# Dev_Board.net
KiCad netlist of a schematic drawn in Altium Designer
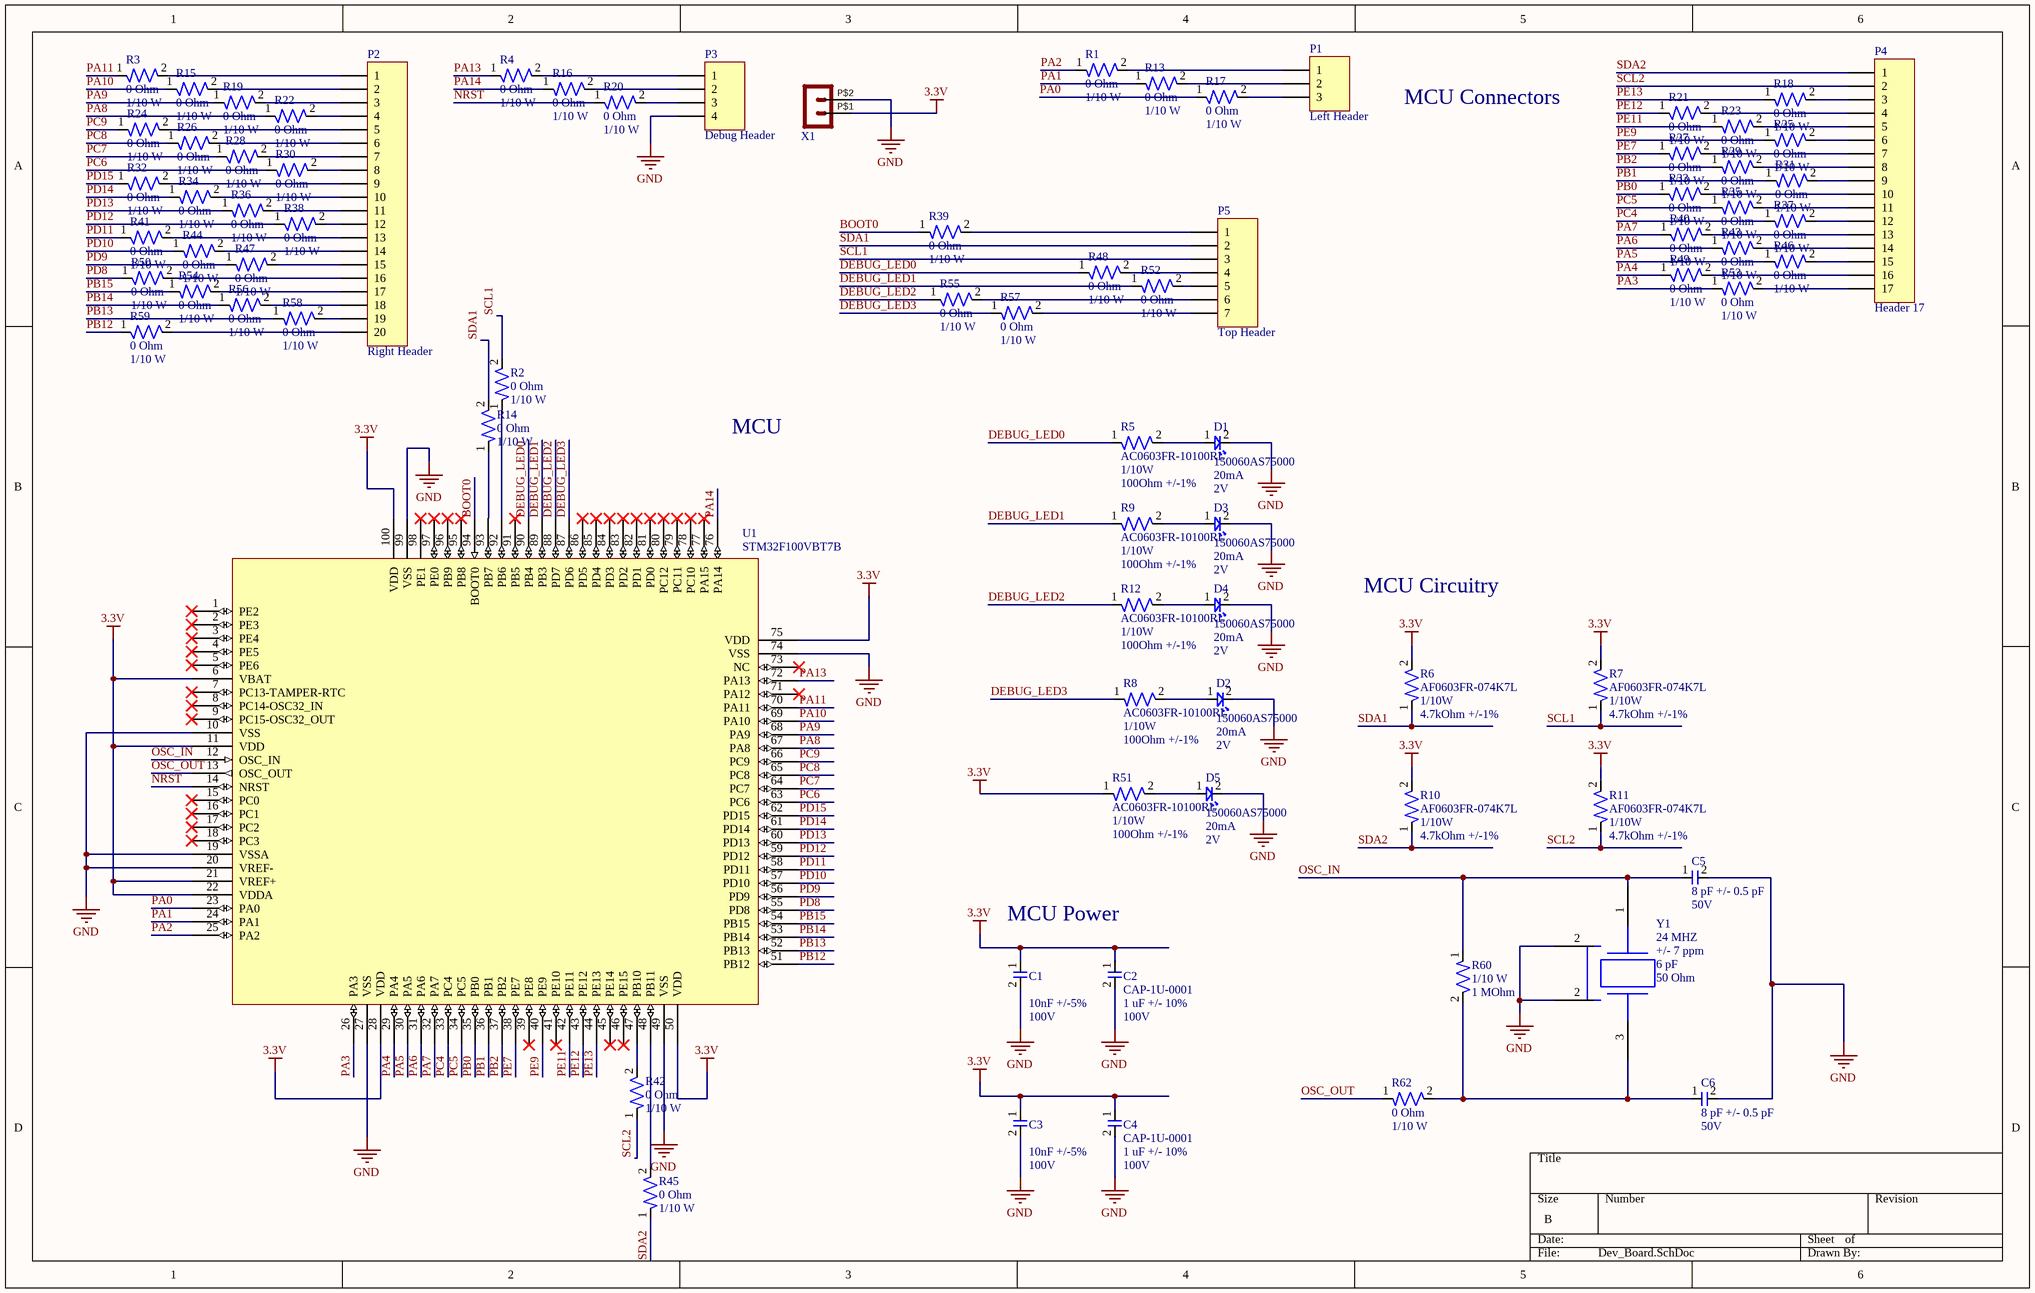
[diagram p0: Dev_Board.SchDoc]

(export (version "E")
  (design (tool "Eeschema 10.0.6"))
  (components
    (comp (ref "C1")
      (value "C1608C0G2A103J080AC")
      (footprint "CAP-0603")
      (description "CAP CER 10000PF 100V C0G 0603")
      (fields
        (field (name "MANUFACTURER") "TDK Corporation")
        (field (name "CAPACITANCE") "10nF +/-5%")
        (field (name "VOLTAGE RATING") "100V")
      )
      (libsource (lib "MasterLib") (part "CAP-10N-0002"))
    )
    (comp (ref "C2")
      (value "CAP-1U-0001")
      (footprint "CAP-1206 - duplicate")
      (description "1 µF ±10% 100V Ceramic Capacitor X7R 1206 (3216 Metric)")
      (fields (field (name "CAPACITANCE") "1 uF +/- 10%") (field (name "VOLTAGE") "100V"))
      (libsource (lib "MasterLib") (part "CAP-1U-0001"))
    )
    (comp (ref "C3")
      (value "C1608C0G2A103J080AC")
      (footprint "CAP-0603")
      (description "CAP CER 10000PF 100V C0G 0603")
      (fields
        (field (name "MANUFACTURER") "TDK Corporation")
        (field (name "CAPACITANCE") "10nF +/-5%")
        (field (name "VOLTAGE RATING") "100V")
      )
      (libsource (lib "MasterLib") (part "CAP-10N-0002"))
    )
    (comp (ref "C4")
      (value "CAP-1U-0001")
      (footprint "CAP-1206 - duplicate")
      (description "1 µF ±10% 100V Ceramic Capacitor X7R 1206 (3216 Metric)")
      (fields (field (name "CAPACITANCE") "1 uF +/- 10%") (field (name "VOLTAGE") "100V"))
      (libsource (lib "MasterLib") (part "CAP-1U-0001"))
    )
    (comp (ref "C5")
      (value "CC0603DRNPO9BN8R0")
      (footprint "CAP-0603")
      (description "8 pF ±0.5pF 50V Ceramic Capacitor C0G, NP0 0603 (1608 Metric)")
      (fields (field (name "CAPACITANCE") "8 pF +/- 0.5 pF") (field (name "VOLTAGE") "50V"))
      (libsource (lib "MasterLib") (part "CAP-8P-0001"))
    )
    (comp (ref "C6")
      (value "CC0603DRNPO9BN8R0")
      (footprint "CAP-0603")
      (description "8 pF ±0.5pF 50V Ceramic Capacitor C0G, NP0 0603 (1608 Metric)")
      (fields (field (name "CAPACITANCE") "8 pF +/- 0.5 pF") (field (name "VOLTAGE") "50V"))
      (libsource (lib "MasterLib") (part "CAP-8P-0001"))
    )
    (comp (ref "D1")
      (value "150060AS75000")
      (footprint "LED-0603")
      (description "CAP CER 0.1UF 100V X7R 0603")
      (fields
        (field (name "MANUFACTURER") "Wurth Electronik")
        (field (name "CURRENT RATING") "20mA")
        (field (name "VF") "2V")
      )
      (libsource (lib "MasterLib") (part "LED_Amber_0001"))
    )
    (comp (ref "D2")
      (value "150060AS75000")
      (footprint "LED-0603")
      (description "CAP CER 0.1UF 100V X7R 0603")
      (fields
        (field (name "MANUFACTURER") "Wurth Electronik")
        (field (name "CURRENT RATING") "20mA")
        (field (name "VF") "2V")
      )
      (libsource (lib "MasterLib") (part "LED_Amber_0001"))
    )
    (comp (ref "D3")
      (value "150060AS75000")
      (footprint "LED-0603")
      (description "CAP CER 0.1UF 100V X7R 0603")
      (fields
        (field (name "MANUFACTURER") "Wurth Electronik")
        (field (name "CURRENT RATING") "20mA")
        (field (name "VF") "2V")
      )
      (libsource (lib "MasterLib") (part "LED_Amber_0001"))
    )
    (comp (ref "D4")
      (value "150060AS75000")
      (footprint "LED-0603")
      (description "CAP CER 0.1UF 100V X7R 0603")
      (fields
        (field (name "MANUFACTURER") "Wurth Electronik")
        (field (name "CURRENT RATING") "20mA")
        (field (name "VF") "2V")
      )
      (libsource (lib "MasterLib") (part "LED_Amber_0001"))
    )
    (comp (ref "D5")
      (value "150060AS75000")
      (footprint "LED-0603")
      (description "CAP CER 0.1UF 100V X7R 0603")
      (fields
        (field (name "MANUFACTURER") "Wurth Electronik")
        (field (name "CURRENT RATING") "20mA")
        (field (name "VF") "2V")
      )
      (libsource (lib "MasterLib") (part "LED_Amber_0001"))
    )
    (comp (ref "P1")
      (value "Left Header")
      (footprint "HDR1X3")
      (description "Header, 3-Pin")
      (fields (field (name "PUBLISHER") "Altium Limited"))
      (libsource (lib "Miscellaneous Connectors") (part "Header 3"))
    )
    (comp (ref "P2")
      (value "Right Header")
      (footprint "HDR1X20")
      (description "Header, 20-Pin")
      (fields (field (name "PUBLISHER") "Altium Limited"))
      (libsource (lib "Miscellaneous Connectors") (part "Header 20"))
    )
    (comp (ref "P3")
      (value "Debug Header")
      (footprint "HDR1X4")
      (description "Header, 4-Pin")
      (fields (field (name "PUBLISHER") "Altium Limited"))
      (libsource (lib "Miscellaneous Connectors") (part "Header 4"))
    )
    (comp (ref "P4")
      (value "Header 17")
      (footprint "HDR1X17")
      (description "Header, 17-Pin")
      (fields (field (name "PUBLISHER") "Altium Limited"))
      (libsource (lib "Miscellaneous Connectors") (part "Header 17"))
    )
    (comp (ref "P5")
      (value "Top Header")
      (footprint "HDR1X7")
      (description "Header, 7-Pin")
      (fields (field (name "PUBLISHER") "Altium Limited"))
      (libsource (lib "Miscellaneous Connectors") (part "Header 7"))
    )
    (comp (ref "R1")
      (value "RMCF0603ZT0R00")
      (footprint "RES-0603")
      (description "0 Ohms Jumper 0.1W, 1/10W Chip Resistor 0603 (1608 Metric) Automotive AEC-Q200 Thick Film")
      (fields (field (name "RESISTANCE") "0 Ohm") (field (name "POWER") "1/10 W"))
      (libsource (lib "MasterLib") (part "RES-0-0001"))
    )
    (comp (ref "R2")
      (value "RMCF0603ZT0R00")
      (footprint "RES-0603")
      (description "0 Ohms Jumper 0.1W, 1/10W Chip Resistor 0603 (1608 Metric) Automotive AEC-Q200 Thick Film")
      (fields (field (name "RESISTANCE") "0 Ohm") (field (name "POWER") "1/10 W"))
      (libsource (lib "MasterLib") (part "RES-0-0001"))
    )
    (comp (ref "R3")
      (value "RMCF0603ZT0R00")
      (footprint "RES-0603")
      (description "0 Ohms Jumper 0.1W, 1/10W Chip Resistor 0603 (1608 Metric) Automotive AEC-Q200 Thick Film")
      (fields (field (name "RESISTANCE") "0 Ohm") (field (name "POWER") "1/10 W"))
      (libsource (lib "MasterLib") (part "RES-0-0001"))
    )
    (comp (ref "R4")
      (value "RMCF0603ZT0R00")
      (footprint "RES-0603")
      (description "0 Ohms Jumper 0.1W, 1/10W Chip Resistor 0603 (1608 Metric) Automotive AEC-Q200 Thick Film")
      (fields (field (name "RESISTANCE") "0 Ohm") (field (name "POWER") "1/10 W"))
      (libsource (lib "MasterLib") (part "RES-0-0001"))
    )
    (comp (ref "R5")
      (value "AC0603FR-10100RL")
      (footprint "RES-0603")
      (description "RESISTOR SMD")
      (fields
        (field (name "MANUFACTURER") "YAGEO")
        (field (name "POWER RATING") "1/10W")
        (field (name "RESISTANCE") "100Ohm +/-1%")
      )
      (libsource (lib "MasterLib") (part "RES-100-0002"))
    )
    (comp (ref "R6")
      (value "AF0603FR-074K7L")
      (footprint "RES-0603")
      (description "RES SMD 4.7K OHM 1% 1/10W 0603")
      (fields
        (field (name "MANUFACTURER") "YAGEO")
        (field (name "POWER RATING") "1/10W")
        (field (name "RESISTANCE") "4.7kOhm +/-1%")
      )
      (libsource (lib "MasterLib") (part "RES-4.7K-0002"))
    )
    (comp (ref "R7")
      (value "AF0603FR-074K7L")
      (footprint "RES-0603")
      (description "RES SMD 4.7K OHM 1% 1/10W 0603")
      (fields
        (field (name "MANUFACTURER") "YAGEO")
        (field (name "POWER RATING") "1/10W")
        (field (name "RESISTANCE") "4.7kOhm +/-1%")
      )
      (libsource (lib "MasterLib") (part "RES-4.7K-0002"))
    )
    (comp (ref "R8")
      (value "AC0603FR-10100RL")
      (footprint "RES-0603")
      (description "RESISTOR SMD")
      (fields
        (field (name "MANUFACTURER") "YAGEO")
        (field (name "POWER RATING") "1/10W")
        (field (name "RESISTANCE") "100Ohm +/-1%")
      )
      (libsource (lib "MasterLib") (part "RES-100-0002"))
    )
    (comp (ref "R9")
      (value "AC0603FR-10100RL")
      (footprint "RES-0603")
      (description "RESISTOR SMD")
      (fields
        (field (name "MANUFACTURER") "YAGEO")
        (field (name "POWER RATING") "1/10W")
        (field (name "RESISTANCE") "100Ohm +/-1%")
      )
      (libsource (lib "MasterLib") (part "RES-100-0002"))
    )
    (comp (ref "R10")
      (value "AF0603FR-074K7L")
      (footprint "RES-0603")
      (description "RES SMD 4.7K OHM 1% 1/10W 0603")
      (fields
        (field (name "MANUFACTURER") "YAGEO")
        (field (name "POWER RATING") "1/10W")
        (field (name "RESISTANCE") "4.7kOhm +/-1%")
      )
      (libsource (lib "MasterLib") (part "RES-4.7K-0002"))
    )
    (comp (ref "R11")
      (value "AF0603FR-074K7L")
      (footprint "RES-0603")
      (description "RES SMD 4.7K OHM 1% 1/10W 0603")
      (fields
        (field (name "MANUFACTURER") "YAGEO")
        (field (name "POWER RATING") "1/10W")
        (field (name "RESISTANCE") "4.7kOhm +/-1%")
      )
      (libsource (lib "MasterLib") (part "RES-4.7K-0002"))
    )
    (comp (ref "R12")
      (value "AC0603FR-10100RL")
      (footprint "RES-0603")
      (description "RESISTOR SMD")
      (fields
        (field (name "MANUFACTURER") "YAGEO")
        (field (name "POWER RATING") "1/10W")
        (field (name "RESISTANCE") "100Ohm +/-1%")
      )
      (libsource (lib "MasterLib") (part "RES-100-0002"))
    )
    (comp (ref "R13")
      (value "RMCF0603ZT0R00")
      (footprint "RES-0603")
      (description "0 Ohms Jumper 0.1W, 1/10W Chip Resistor 0603 (1608 Metric) Automotive AEC-Q200 Thick Film")
      (fields (field (name "RESISTANCE") "0 Ohm") (field (name "POWER") "1/10 W"))
      (libsource (lib "MasterLib") (part "RES-0-0001"))
    )
    (comp (ref "R14")
      (value "RMCF0603ZT0R00")
      (footprint "RES-0603")
      (description "0 Ohms Jumper 0.1W, 1/10W Chip Resistor 0603 (1608 Metric) Automotive AEC-Q200 Thick Film")
      (fields (field (name "RESISTANCE") "0 Ohm") (field (name "POWER") "1/10 W"))
      (libsource (lib "MasterLib") (part "RES-0-0001"))
    )
    (comp (ref "R15")
      (value "RMCF0603ZT0R00")
      (footprint "RES-0603")
      (description "0 Ohms Jumper 0.1W, 1/10W Chip Resistor 0603 (1608 Metric) Automotive AEC-Q200 Thick Film")
      (fields (field (name "RESISTANCE") "0 Ohm") (field (name "POWER") "1/10 W"))
      (libsource (lib "MasterLib") (part "RES-0-0001"))
    )
    (comp (ref "R16")
      (value "RMCF0603ZT0R00")
      (footprint "RES-0603")
      (description "0 Ohms Jumper 0.1W, 1/10W Chip Resistor 0603 (1608 Metric) Automotive AEC-Q200 Thick Film")
      (fields (field (name "RESISTANCE") "0 Ohm") (field (name "POWER") "1/10 W"))
      (libsource (lib "MasterLib") (part "RES-0-0001"))
    )
    (comp (ref "R17")
      (value "RMCF0603ZT0R00")
      (footprint "RES-0603")
      (description "0 Ohms Jumper 0.1W, 1/10W Chip Resistor 0603 (1608 Metric) Automotive AEC-Q200 Thick Film")
      (fields (field (name "RESISTANCE") "0 Ohm") (field (name "POWER") "1/10 W"))
      (libsource (lib "MasterLib") (part "RES-0-0001"))
    )
    (comp (ref "R18")
      (value "RMCF0603ZT0R00")
      (footprint "RES-0603")
      (description "0 Ohms Jumper 0.1W, 1/10W Chip Resistor 0603 (1608 Metric) Automotive AEC-Q200 Thick Film")
      (fields (field (name "RESISTANCE") "0 Ohm") (field (name "POWER") "1/10 W"))
      (libsource (lib "MasterLib") (part "RES-0-0001"))
    )
    (comp (ref "R19")
      (value "RMCF0603ZT0R00")
      (footprint "RES-0603")
      (description "0 Ohms Jumper 0.1W, 1/10W Chip Resistor 0603 (1608 Metric) Automotive AEC-Q200 Thick Film")
      (fields (field (name "RESISTANCE") "0 Ohm") (field (name "POWER") "1/10 W"))
      (libsource (lib "MasterLib") (part "RES-0-0001"))
    )
    (comp (ref "R20")
      (value "RMCF0603ZT0R00")
      (footprint "RES-0603")
      (description "0 Ohms Jumper 0.1W, 1/10W Chip Resistor 0603 (1608 Metric) Automotive AEC-Q200 Thick Film")
      (fields (field (name "RESISTANCE") "0 Ohm") (field (name "POWER") "1/10 W"))
      (libsource (lib "MasterLib") (part "RES-0-0001"))
    )
    (comp (ref "R21")
      (value "RMCF0603ZT0R00")
      (footprint "RES-0603")
      (description "0 Ohms Jumper 0.1W, 1/10W Chip Resistor 0603 (1608 Metric) Automotive AEC-Q200 Thick Film")
      (fields (field (name "RESISTANCE") "0 Ohm") (field (name "POWER") "1/10 W"))
      (libsource (lib "MasterLib") (part "RES-0-0001"))
    )
    (comp (ref "R22")
      (value "RMCF0603ZT0R00")
      (footprint "RES-0603")
      (description "0 Ohms Jumper 0.1W, 1/10W Chip Resistor 0603 (1608 Metric) Automotive AEC-Q200 Thick Film")
      (fields (field (name "RESISTANCE") "0 Ohm") (field (name "POWER") "1/10 W"))
      (libsource (lib "MasterLib") (part "RES-0-0001"))
    )
    (comp (ref "R23")
      (value "RMCF0603ZT0R00")
      (footprint "RES-0603")
      (description "0 Ohms Jumper 0.1W, 1/10W Chip Resistor 0603 (1608 Metric) Automotive AEC-Q200 Thick Film")
      (fields (field (name "RESISTANCE") "0 Ohm") (field (name "POWER") "1/10 W"))
      (libsource (lib "MasterLib") (part "RES-0-0001"))
    )
    (comp (ref "R24")
      (value "RMCF0603ZT0R00")
      (footprint "RES-0603")
      (description "0 Ohms Jumper 0.1W, 1/10W Chip Resistor 0603 (1608 Metric) Automotive AEC-Q200 Thick Film")
      (fields (field (name "RESISTANCE") "0 Ohm") (field (name "POWER") "1/10 W"))
      (libsource (lib "MasterLib") (part "RES-0-0001"))
    )
    (comp (ref "R25")
      (value "RMCF0603ZT0R00")
      (footprint "RES-0603")
      (description "0 Ohms Jumper 0.1W, 1/10W Chip Resistor 0603 (1608 Metric) Automotive AEC-Q200 Thick Film")
      (fields (field (name "RESISTANCE") "0 Ohm") (field (name "POWER") "1/10 W"))
      (libsource (lib "MasterLib") (part "RES-0-0001"))
    )
    (comp (ref "R26")
      (value "RMCF0603ZT0R00")
      (footprint "RES-0603")
      (description "0 Ohms Jumper 0.1W, 1/10W Chip Resistor 0603 (1608 Metric) Automotive AEC-Q200 Thick Film")
      (fields (field (name "RESISTANCE") "0 Ohm") (field (name "POWER") "1/10 W"))
      (libsource (lib "MasterLib") (part "RES-0-0001"))
    )
    (comp (ref "R27")
      (value "RMCF0603ZT0R00")
      (footprint "RES-0603")
      (description "0 Ohms Jumper 0.1W, 1/10W Chip Resistor 0603 (1608 Metric) Automotive AEC-Q200 Thick Film")
      (fields (field (name "RESISTANCE") "0 Ohm") (field (name "POWER") "1/10 W"))
      (libsource (lib "MasterLib") (part "RES-0-0001"))
    )
    (comp (ref "R28")
      (value "RMCF0603ZT0R00")
      (footprint "RES-0603")
      (description "0 Ohms Jumper 0.1W, 1/10W Chip Resistor 0603 (1608 Metric) Automotive AEC-Q200 Thick Film")
      (fields (field (name "RESISTANCE") "0 Ohm") (field (name "POWER") "1/10 W"))
      (libsource (lib "MasterLib") (part "RES-0-0001"))
    )
    (comp (ref "R29")
      (value "RMCF0603ZT0R00")
      (footprint "RES-0603")
      (description "0 Ohms Jumper 0.1W, 1/10W Chip Resistor 0603 (1608 Metric) Automotive AEC-Q200 Thick Film")
      (fields (field (name "RESISTANCE") "0 Ohm") (field (name "POWER") "1/10 W"))
      (libsource (lib "MasterLib") (part "RES-0-0001"))
    )
    (comp (ref "R30")
      (value "RMCF0603ZT0R00")
      (footprint "RES-0603")
      (description "0 Ohms Jumper 0.1W, 1/10W Chip Resistor 0603 (1608 Metric) Automotive AEC-Q200 Thick Film")
      (fields (field (name "RESISTANCE") "0 Ohm") (field (name "POWER") "1/10 W"))
      (libsource (lib "MasterLib") (part "RES-0-0001"))
    )
    (comp (ref "R31")
      (value "RMCF0603ZT0R00")
      (footprint "RES-0603")
      (description "0 Ohms Jumper 0.1W, 1/10W Chip Resistor 0603 (1608 Metric) Automotive AEC-Q200 Thick Film")
      (fields (field (name "RESISTANCE") "0 Ohm") (field (name "POWER") "1/10 W"))
      (libsource (lib "MasterLib") (part "RES-0-0001"))
    )
    (comp (ref "R32")
      (value "RMCF0603ZT0R00")
      (footprint "RES-0603")
      (description "0 Ohms Jumper 0.1W, 1/10W Chip Resistor 0603 (1608 Metric) Automotive AEC-Q200 Thick Film")
      (fields (field (name "RESISTANCE") "0 Ohm") (field (name "POWER") "1/10 W"))
      (libsource (lib "MasterLib") (part "RES-0-0001"))
    )
    (comp (ref "R33")
      (value "RMCF0603ZT0R00")
      (footprint "RES-0603")
      (description "0 Ohms Jumper 0.1W, 1/10W Chip Resistor 0603 (1608 Metric) Automotive AEC-Q200 Thick Film")
      (fields (field (name "RESISTANCE") "0 Ohm") (field (name "POWER") "1/10 W"))
      (libsource (lib "MasterLib") (part "RES-0-0001"))
    )
    (comp (ref "R34")
      (value "RMCF0603ZT0R00")
      (footprint "RES-0603")
      (description "0 Ohms Jumper 0.1W, 1/10W Chip Resistor 0603 (1608 Metric) Automotive AEC-Q200 Thick Film")
      (fields (field (name "RESISTANCE") "0 Ohm") (field (name "POWER") "1/10 W"))
      (libsource (lib "MasterLib") (part "RES-0-0001"))
    )
    (comp (ref "R35")
      (value "RMCF0603ZT0R00")
      (footprint "RES-0603")
      (description "0 Ohms Jumper 0.1W, 1/10W Chip Resistor 0603 (1608 Metric) Automotive AEC-Q200 Thick Film")
      (fields (field (name "RESISTANCE") "0 Ohm") (field (name "POWER") "1/10 W"))
      (libsource (lib "MasterLib") (part "RES-0-0001"))
    )
    (comp (ref "R36")
      (value "RMCF0603ZT0R00")
      (footprint "RES-0603")
      (description "0 Ohms Jumper 0.1W, 1/10W Chip Resistor 0603 (1608 Metric) Automotive AEC-Q200 Thick Film")
      (fields (field (name "RESISTANCE") "0 Ohm") (field (name "POWER") "1/10 W"))
      (libsource (lib "MasterLib") (part "RES-0-0001"))
    )
    (comp (ref "R37")
      (value "RMCF0603ZT0R00")
      (footprint "RES-0603")
      (description "0 Ohms Jumper 0.1W, 1/10W Chip Resistor 0603 (1608 Metric) Automotive AEC-Q200 Thick Film")
      (fields (field (name "RESISTANCE") "0 Ohm") (field (name "POWER") "1/10 W"))
      (libsource (lib "MasterLib") (part "RES-0-0001"))
    )
    (comp (ref "R38")
      (value "RMCF0603ZT0R00")
      (footprint "RES-0603")
      (description "0 Ohms Jumper 0.1W, 1/10W Chip Resistor 0603 (1608 Metric) Automotive AEC-Q200 Thick Film")
      (fields (field (name "RESISTANCE") "0 Ohm") (field (name "POWER") "1/10 W"))
      (libsource (lib "MasterLib") (part "RES-0-0001"))
    )
    (comp (ref "R39")
      (value "RMCF0603ZT0R00")
      (footprint "RES-0603")
      (description "0 Ohms Jumper 0.1W, 1/10W Chip Resistor 0603 (1608 Metric) Automotive AEC-Q200 Thick Film")
      (fields (field (name "RESISTANCE") "0 Ohm") (field (name "POWER") "1/10 W"))
      (libsource (lib "MasterLib") (part "RES-0-0001"))
    )
    (comp (ref "R40")
      (value "RMCF0603ZT0R00")
      (footprint "RES-0603")
      (description "0 Ohms Jumper 0.1W, 1/10W Chip Resistor 0603 (1608 Metric) Automotive AEC-Q200 Thick Film")
      (fields (field (name "RESISTANCE") "0 Ohm") (field (name "POWER") "1/10 W"))
      (libsource (lib "MasterLib") (part "RES-0-0001"))
    )
    (comp (ref "R41")
      (value "RMCF0603ZT0R00")
      (footprint "RES-0603")
      (description "0 Ohms Jumper 0.1W, 1/10W Chip Resistor 0603 (1608 Metric) Automotive AEC-Q200 Thick Film")
      (fields (field (name "RESISTANCE") "0 Ohm") (field (name "POWER") "1/10 W"))
      (libsource (lib "MasterLib") (part "RES-0-0001"))
    )
    (comp (ref "R42")
      (value "RMCF0603ZT0R00")
      (footprint "RES-0603")
      (description "0 Ohms Jumper 0.1W, 1/10W Chip Resistor 0603 (1608 Metric) Automotive AEC-Q200 Thick Film")
      (fields (field (name "RESISTANCE") "0 Ohm") (field (name "POWER") "1/10 W"))
      (libsource (lib "MasterLib") (part "RES-0-0001"))
    )
    (comp (ref "R43")
      (value "RMCF0603ZT0R00")
      (footprint "RES-0603")
      (description "0 Ohms Jumper 0.1W, 1/10W Chip Resistor 0603 (1608 Metric) Automotive AEC-Q200 Thick Film")
      (fields (field (name "RESISTANCE") "0 Ohm") (field (name "POWER") "1/10 W"))
      (libsource (lib "MasterLib") (part "RES-0-0001"))
    )
    (comp (ref "R44")
      (value "RMCF0603ZT0R00")
      (footprint "RES-0603")
      (description "0 Ohms Jumper 0.1W, 1/10W Chip Resistor 0603 (1608 Metric) Automotive AEC-Q200 Thick Film")
      (fields (field (name "RESISTANCE") "0 Ohm") (field (name "POWER") "1/10 W"))
      (libsource (lib "MasterLib") (part "RES-0-0001"))
    )
    (comp (ref "R45")
      (value "RMCF0603ZT0R00")
      (footprint "RES-0603")
      (description "0 Ohms Jumper 0.1W, 1/10W Chip Resistor 0603 (1608 Metric) Automotive AEC-Q200 Thick Film")
      (fields (field (name "RESISTANCE") "0 Ohm") (field (name "POWER") "1/10 W"))
      (libsource (lib "MasterLib") (part "RES-0-0001"))
    )
    (comp (ref "R46")
      (value "RMCF0603ZT0R00")
      (footprint "RES-0603")
      (description "0 Ohms Jumper 0.1W, 1/10W Chip Resistor 0603 (1608 Metric) Automotive AEC-Q200 Thick Film")
      (fields (field (name "RESISTANCE") "0 Ohm") (field (name "POWER") "1/10 W"))
      (libsource (lib "MasterLib") (part "RES-0-0001"))
    )
    (comp (ref "R47")
      (value "RMCF0603ZT0R00")
      (footprint "RES-0603")
      (description "0 Ohms Jumper 0.1W, 1/10W Chip Resistor 0603 (1608 Metric) Automotive AEC-Q200 Thick Film")
      (fields (field (name "RESISTANCE") "0 Ohm") (field (name "POWER") "1/10 W"))
      (libsource (lib "MasterLib") (part "RES-0-0001"))
    )
    (comp (ref "R48")
      (value "RMCF0603ZT0R00")
      (footprint "RES-0603")
      (description "0 Ohms Jumper 0.1W, 1/10W Chip Resistor 0603 (1608 Metric) Automotive AEC-Q200 Thick Film")
      (fields (field (name "RESISTANCE") "0 Ohm") (field (name "POWER") "1/10 W"))
      (libsource (lib "MasterLib") (part "RES-0-0001"))
    )
    (comp (ref "R49")
      (value "RMCF0603ZT0R00")
      (footprint "RES-0603")
      (description "0 Ohms Jumper 0.1W, 1/10W Chip Resistor 0603 (1608 Metric) Automotive AEC-Q200 Thick Film")
      (fields (field (name "RESISTANCE") "0 Ohm") (field (name "POWER") "1/10 W"))
      (libsource (lib "MasterLib") (part "RES-0-0001"))
    )
    (comp (ref "R50")
      (value "RMCF0603ZT0R00")
      (footprint "RES-0603")
      (description "0 Ohms Jumper 0.1W, 1/10W Chip Resistor 0603 (1608 Metric) Automotive AEC-Q200 Thick Film")
      (fields (field (name "RESISTANCE") "0 Ohm") (field (name "POWER") "1/10 W"))
      (libsource (lib "MasterLib") (part "RES-0-0001"))
    )
    (comp (ref "R51")
      (value "AC0603FR-10100RL")
      (footprint "RES-0603")
      (description "RESISTOR SMD")
      (fields
        (field (name "MANUFACTURER") "YAGEO")
        (field (name "POWER RATING") "1/10W")
        (field (name "RESISTANCE") "100Ohm +/-1%")
      )
      (libsource (lib "MasterLib") (part "RES-100-0002"))
    )
    (comp (ref "R52")
      (value "RMCF0603ZT0R00")
      (footprint "RES-0603")
      (description "0 Ohms Jumper 0.1W, 1/10W Chip Resistor 0603 (1608 Metric) Automotive AEC-Q200 Thick Film")
      (fields (field (name "RESISTANCE") "0 Ohm") (field (name "POWER") "1/10 W"))
      (libsource (lib "MasterLib") (part "RES-0-0001"))
    )
    (comp (ref "R53")
      (value "RMCF0603ZT0R00")
      (footprint "RES-0603")
      (description "0 Ohms Jumper 0.1W, 1/10W Chip Resistor 0603 (1608 Metric) Automotive AEC-Q200 Thick Film")
      (fields (field (name "RESISTANCE") "0 Ohm") (field (name "POWER") "1/10 W"))
      (libsource (lib "MasterLib") (part "RES-0-0001"))
    )
    (comp (ref "R54")
      (value "RMCF0603ZT0R00")
      (footprint "RES-0603")
      (description "0 Ohms Jumper 0.1W, 1/10W Chip Resistor 0603 (1608 Metric) Automotive AEC-Q200 Thick Film")
      (fields (field (name "RESISTANCE") "0 Ohm") (field (name "POWER") "1/10 W"))
      (libsource (lib "MasterLib") (part "RES-0-0001"))
    )
    (comp (ref "R55")
      (value "RMCF0603ZT0R00")
      (footprint "RES-0603")
      (description "0 Ohms Jumper 0.1W, 1/10W Chip Resistor 0603 (1608 Metric) Automotive AEC-Q200 Thick Film")
      (fields (field (name "RESISTANCE") "0 Ohm") (field (name "POWER") "1/10 W"))
      (libsource (lib "MasterLib") (part "RES-0-0001"))
    )
    (comp (ref "R56")
      (value "RMCF0603ZT0R00")
      (footprint "RES-0603")
      (description "0 Ohms Jumper 0.1W, 1/10W Chip Resistor 0603 (1608 Metric) Automotive AEC-Q200 Thick Film")
      (fields (field (name "RESISTANCE") "0 Ohm") (field (name "POWER") "1/10 W"))
      (libsource (lib "MasterLib") (part "RES-0-0001"))
    )
    (comp (ref "R57")
      (value "RMCF0603ZT0R00")
      (footprint "RES-0603")
      (description "0 Ohms Jumper 0.1W, 1/10W Chip Resistor 0603 (1608 Metric) Automotive AEC-Q200 Thick Film")
      (fields (field (name "RESISTANCE") "0 Ohm") (field (name "POWER") "1/10 W"))
      (libsource (lib "MasterLib") (part "RES-0-0001"))
    )
    (comp (ref "R58")
      (value "RMCF0603ZT0R00")
      (footprint "RES-0603")
      (description "0 Ohms Jumper 0.1W, 1/10W Chip Resistor 0603 (1608 Metric) Automotive AEC-Q200 Thick Film")
      (fields (field (name "RESISTANCE") "0 Ohm") (field (name "POWER") "1/10 W"))
      (libsource (lib "MasterLib") (part "RES-0-0001"))
    )
    (comp (ref "R59")
      (value "RMCF0603ZT0R00")
      (footprint "RES-0603")
      (description "0 Ohms Jumper 0.1W, 1/10W Chip Resistor 0603 (1608 Metric) Automotive AEC-Q200 Thick Film")
      (fields (field (name "RESISTANCE") "0 Ohm") (field (name "POWER") "1/10 W"))
      (libsource (lib "MasterLib") (part "RES-0-0001"))
    )
    (comp (ref "R60")
      (value "RMCF0603FT1M00")
      (footprint "RES-0603")
      (description "1 MOhms ±1% 0.1W, 1/10W Chip Resistor 0603 (1608 Metric) Automotive AEC-Q200 Thick Film")
      (fields (field (name "POWER") "1/10 W") (field (name "RESISTANCE") "1 MOhm"))
      (libsource (lib "MasterLib") (part "RES-1M-0001"))
    )
    (comp (ref "R62")
      (value "RMCF0603ZT0R00")
      (footprint "RES-0603")
      (description "0 Ohms Jumper 0.1W, 1/10W Chip Resistor 0603 (1608 Metric) Automotive AEC-Q200 Thick Film")
      (fields (field (name "RESISTANCE") "0 Ohm") (field (name "POWER") "1/10 W"))
      (libsource (lib "MasterLib") (part "RES-0-0001"))
    )
    (comp (ref "U1")
      (value "STM32F100VBT7B")
      (footprint "IC-STM32F100-0001")
      (libsource (lib "MasterLib") (part "IC-STM32F100-0001"))
    )
    (comp (ref "X1")
      (value "Molex - Micro-Fit 3.0 Series connector,  3.00mm (0.118\") pitch header, 2 positions.")
      (footprint "43650-0200")
      (libsource (lib "Molex Microfit") (part "HEADER_POS2_?43650-0200"))
    )
    (comp (ref "Y1")
      (value "ECS-240-6-37B-7KM-TR")
      (footprint "CRYSTAL-4-SMD-0001")
      (description "24 MHz ±7ppm Crystal 6pF 50 Ohms 4-SMD, No Lead")
      (fields
        (field (name "MANUFACTURER") "ECS Inc.")
        (field (name "FREQUENCY") "24 MHZ")
        (field (name "FREQUENCY TOLERANCE") "+/- 7 ppm")
        (field (name "LOAD CAPACITANCE") "6 pF")
        (field (name "EQUAVALENCE SERIES RESISTANCE") "50 Ohm")
      )
      (libsource (lib "MasterLib") (part "CRYSTAL-24MHz-0001"))
    )
  )
  (nets
    (net (code "1") (name "/BOOT0") (class "Default")
      (node (ref "R39") (pin "1") (pinfunction "1_1") (pintype "passive"))
      (node (ref "U1") (pin "94") (pinfunction "BOOT0_94") (pintype "input"))
    )
    (net (code "2") (name "/DEBUG_LED0") (class "Default")
      (node (ref "R48") (pin "1") (pinfunction "1_1") (pintype "passive"))
      (node (ref "R5") (pin "1") (pinfunction "1_1") (pintype "passive"))
      (node (ref "U1") (pin "90") (pinfunction "PB4_90") (pintype "bidirectional"))
    )
    (net (code "3") (name "/DEBUG_LED1") (class "Default")
      (node (ref "R52") (pin "1") (pinfunction "1_1") (pintype "passive"))
      (node (ref "R9") (pin "1") (pinfunction "1_1") (pintype "passive"))
      (node (ref "U1") (pin "89") (pinfunction "PB3_89") (pintype "bidirectional"))
    )
    (net (code "4") (name "/DEBUG_LED2") (class "Default")
      (node (ref "R12") (pin "1") (pinfunction "1_1") (pintype "passive"))
      (node (ref "R55") (pin "1") (pinfunction "1_1") (pintype "passive"))
      (node (ref "U1") (pin "88") (pinfunction "PD7_88") (pintype "bidirectional"))
    )
    (net (code "5") (name "/DEBUG_LED3") (class "Default")
      (node (ref "R57") (pin "1") (pinfunction "1_1") (pintype "passive"))
      (node (ref "R8") (pin "1") (pinfunction "1_1") (pintype "passive"))
      (node (ref "U1") (pin "87") (pinfunction "PD6_87") (pintype "bidirectional"))
    )
    (net (code "6") (name "/NRST") (class "Default")
      (node (ref "R20") (pin "1") (pinfunction "1_1") (pintype "passive"))
      (node (ref "U1") (pin "14") (pinfunction "NRST_14") (pintype "bidirectional"))
    )
    (net (code "7") (name "/OSC_IN") (class "Default")
      (node (ref "C5") (pin "1") (pinfunction "1_1") (pintype "passive"))
      (node (ref "R60") (pin "1") (pinfunction "1_1") (pintype "passive"))
      (node (ref "U1") (pin "12") (pinfunction "OSC_IN_12") (pintype "input"))
      (node (ref "Y1") (pin "1") (pinfunction "1_1") (pintype "passive"))
    )
    (net (code "8") (name "/OSC_OUT") (class "Default")
      (node (ref "R62") (pin "1") (pinfunction "1_1") (pintype "passive"))
      (node (ref "U1") (pin "13") (pinfunction "OSC_OUT_13") (pintype "output"))
    )
    (net (code "9") (name "/PA0") (class "Default")
      (node (ref "R17") (pin "1") (pinfunction "1_1") (pintype "passive"))
      (node (ref "U1") (pin "23") (pinfunction "PA0_23") (pintype "bidirectional"))
    )
    (net (code "10") (name "/PA1") (class "Default")
      (node (ref "R13") (pin "1") (pinfunction "1_1") (pintype "passive"))
      (node (ref "U1") (pin "24") (pinfunction "PA1_24") (pintype "bidirectional"))
    )
    (net (code "11") (name "/PA2") (class "Default")
      (node (ref "R1") (pin "1") (pinfunction "1_1") (pintype "passive"))
      (node (ref "U1") (pin "25") (pinfunction "PA2_25") (pintype "bidirectional"))
    )
    (net (code "12") (name "/PA3") (class "Default")
      (node (ref "R53") (pin "1") (pinfunction "1_1") (pintype "passive"))
      (node (ref "U1") (pin "26") (pinfunction "PA3_26") (pintype "bidirectional"))
    )
    (net (code "13") (name "/PA4") (class "Default")
      (node (ref "R49") (pin "1") (pinfunction "1_1") (pintype "passive"))
      (node (ref "U1") (pin "29") (pinfunction "PA4_29") (pintype "bidirectional"))
    )
    (net (code "14") (name "/PA5") (class "Default")
      (node (ref "R46") (pin "1") (pinfunction "1_1") (pintype "passive"))
      (node (ref "U1") (pin "30") (pinfunction "PA5_30") (pintype "bidirectional"))
    )
    (net (code "15") (name "/PA6") (class "Default")
      (node (ref "R43") (pin "1") (pinfunction "1_1") (pintype "passive"))
      (node (ref "U1") (pin "31") (pinfunction "PA6_31") (pintype "bidirectional"))
    )
    (net (code "16") (name "/PA7") (class "Default")
      (node (ref "R40") (pin "1") (pinfunction "1_1") (pintype "passive"))
      (node (ref "U1") (pin "32") (pinfunction "PA7_32") (pintype "bidirectional"))
    )
    (net (code "17") (name "/PA8") (class "Default")
      (node (ref "R22") (pin "1") (pinfunction "1_1") (pintype "passive"))
      (node (ref "U1") (pin "67") (pinfunction "PA8_67") (pintype "bidirectional"))
    )
    (net (code "18") (name "/PA9") (class "Default")
      (node (ref "R19") (pin "1") (pinfunction "1_1") (pintype "passive"))
      (node (ref "U1") (pin "68") (pinfunction "PA9_68") (pintype "bidirectional"))
    )
    (net (code "19") (name "/PA10") (class "Default")
      (node (ref "R15") (pin "1") (pinfunction "1_1") (pintype "passive"))
      (node (ref "U1") (pin "69") (pinfunction "PA10_69") (pintype "bidirectional"))
    )
    (net (code "20") (name "/PA11") (class "Default")
      (node (ref "R3") (pin "1") (pinfunction "1_1") (pintype "passive"))
      (node (ref "U1") (pin "70") (pinfunction "PA11_70") (pintype "bidirectional"))
    )
    (net (code "21") (name "/PA13") (class "Default")
      (node (ref "R4") (pin "1") (pinfunction "1_1") (pintype "passive"))
      (node (ref "U1") (pin "72") (pinfunction "PA13_72") (pintype "bidirectional"))
    )
    (net (code "22") (name "/PA14") (class "Default")
      (node (ref "R16") (pin "1") (pinfunction "1_1") (pintype "passive"))
      (node (ref "U1") (pin "76") (pinfunction "PA14_76") (pintype "bidirectional"))
    )
    (net (code "23") (name "/PB0") (class "Default")
      (node (ref "R33") (pin "1") (pinfunction "1_1") (pintype "passive"))
      (node (ref "U1") (pin "35") (pinfunction "PB0_35") (pintype "bidirectional"))
    )
    (net (code "24") (name "/PB1") (class "Default")
      (node (ref "R31") (pin "1") (pinfunction "1_1") (pintype "passive"))
      (node (ref "U1") (pin "36") (pinfunction "PB1_36") (pintype "bidirectional"))
    )
    (net (code "25") (name "/PB2") (class "Default")
      (node (ref "R29") (pin "1") (pinfunction "1_1") (pintype "passive"))
      (node (ref "U1") (pin "37") (pinfunction "PB2_37") (pintype "bidirectional"))
    )
    (net (code "26") (name "/PB12") (class "Default")
      (node (ref "R59") (pin "1") (pinfunction "1_1") (pintype "passive"))
      (node (ref "U1") (pin "51") (pinfunction "PB12_51") (pintype "bidirectional"))
    )
    (net (code "27") (name "/PB13") (class "Default")
      (node (ref "R58") (pin "1") (pinfunction "1_1") (pintype "passive"))
      (node (ref "U1") (pin "52") (pinfunction "PB13_52") (pintype "bidirectional"))
    )
    (net (code "28") (name "/PB14") (class "Default")
      (node (ref "R56") (pin "1") (pinfunction "1_1") (pintype "passive"))
      (node (ref "U1") (pin "53") (pinfunction "PB14_53") (pintype "bidirectional"))
    )
    (net (code "29") (name "/PB15") (class "Default")
      (node (ref "R54") (pin "1") (pinfunction "1_1") (pintype "passive"))
      (node (ref "U1") (pin "54") (pinfunction "PB15_54") (pintype "bidirectional"))
    )
    (net (code "30") (name "/PC4") (class "Default")
      (node (ref "R37") (pin "1") (pinfunction "1_1") (pintype "passive"))
      (node (ref "U1") (pin "33") (pinfunction "PC4_33") (pintype "bidirectional"))
    )
    (net (code "31") (name "/PC5") (class "Default")
      (node (ref "R35") (pin "1") (pinfunction "1_1") (pintype "passive"))
      (node (ref "U1") (pin "34") (pinfunction "PC5_34") (pintype "bidirectional"))
    )
    (net (code "32") (name "/PC6") (class "Default")
      (node (ref "R30") (pin "1") (pinfunction "1_1") (pintype "passive"))
      (node (ref "U1") (pin "63") (pinfunction "PC6_63") (pintype "bidirectional"))
    )
    (net (code "33") (name "/PC7") (class "Default")
      (node (ref "R28") (pin "1") (pinfunction "1_1") (pintype "passive"))
      (node (ref "U1") (pin "64") (pinfunction "PC7_64") (pintype "bidirectional"))
    )
    (net (code "34") (name "/PC8") (class "Default")
      (node (ref "R26") (pin "1") (pinfunction "1_1") (pintype "passive"))
      (node (ref "U1") (pin "65") (pinfunction "PC8_65") (pintype "bidirectional"))
    )
    (net (code "35") (name "/PC9") (class "Default")
      (node (ref "R24") (pin "1") (pinfunction "1_1") (pintype "passive"))
      (node (ref "U1") (pin "66") (pinfunction "PC9_66") (pintype "bidirectional"))
    )
    (net (code "36") (name "/PD8") (class "Default")
      (node (ref "R50") (pin "1") (pinfunction "1_1") (pintype "passive"))
      (node (ref "U1") (pin "55") (pinfunction "PD8_55") (pintype "bidirectional"))
    )
    (net (code "37") (name "/PD9") (class "Default")
      (node (ref "R47") (pin "1") (pinfunction "1_1") (pintype "passive"))
      (node (ref "U1") (pin "56") (pinfunction "PD9_56") (pintype "bidirectional"))
    )
    (net (code "38") (name "/PD10") (class "Default")
      (node (ref "R44") (pin "1") (pinfunction "1_1") (pintype "passive"))
      (node (ref "U1") (pin "57") (pinfunction "PD10_57") (pintype "bidirectional"))
    )
    (net (code "39") (name "/PD11") (class "Default")
      (node (ref "R41") (pin "1") (pinfunction "1_1") (pintype "passive"))
      (node (ref "U1") (pin "58") (pinfunction "PD11_58") (pintype "bidirectional"))
    )
    (net (code "40") (name "/PD12") (class "Default")
      (node (ref "R38") (pin "1") (pinfunction "1_1") (pintype "passive"))
      (node (ref "U1") (pin "59") (pinfunction "PD12_59") (pintype "bidirectional"))
    )
    (net (code "41") (name "/PD13") (class "Default")
      (node (ref "R36") (pin "1") (pinfunction "1_1") (pintype "passive"))
      (node (ref "U1") (pin "60") (pinfunction "PD13_60") (pintype "bidirectional"))
    )
    (net (code "42") (name "/PD14") (class "Default")
      (node (ref "R34") (pin "1") (pinfunction "1_1") (pintype "passive"))
      (node (ref "U1") (pin "61") (pinfunction "PD14_61") (pintype "bidirectional"))
    )
    (net (code "43") (name "/PD15") (class "Default")
      (node (ref "R32") (pin "1") (pinfunction "1_1") (pintype "passive"))
      (node (ref "U1") (pin "62") (pinfunction "PD15_62") (pintype "bidirectional"))
    )
    (net (code "44") (name "/PE7") (class "Default")
      (node (ref "R27") (pin "1") (pinfunction "1_1") (pintype "passive"))
      (node (ref "U1") (pin "38") (pinfunction "PE7_38") (pintype "bidirectional"))
    )
    (net (code "45") (name "/PE9") (class "Default")
      (node (ref "R25") (pin "1") (pinfunction "1_1") (pintype "passive"))
      (node (ref "U1") (pin "40") (pinfunction "PE9_40") (pintype "bidirectional"))
    )
    (net (code "46") (name "/PE11") (class "Default")
      (node (ref "R23") (pin "1") (pinfunction "1_1") (pintype "passive"))
      (node (ref "U1") (pin "42") (pinfunction "PE11_42") (pintype "bidirectional"))
    )
    (net (code "47") (name "/PE12") (class "Default")
      (node (ref "R21") (pin "1") (pinfunction "1_1") (pintype "passive"))
      (node (ref "U1") (pin "43") (pinfunction "PE12_43") (pintype "bidirectional"))
    )
    (net (code "48") (name "/PE13") (class "Default")
      (node (ref "R18") (pin "1") (pinfunction "1_1") (pintype "passive"))
      (node (ref "U1") (pin "44") (pinfunction "PE13_44") (pintype "bidirectional"))
    )
    (net (code "49") (name "/SCL1") (class "Default")
      (node (ref "P5") (pin "3") (pinfunction "3_3") (pintype "passive"))
      (node (ref "R2") (pin "2") (pinfunction "2_2") (pintype "passive"))
      (node (ref "R7") (pin "1") (pinfunction "1_1") (pintype "passive"))
    )
    (net (code "50") (name "/SCL2") (class "Default")
      (node (ref "P4") (pin "2") (pinfunction "2_2") (pintype "passive"))
      (node (ref "R11") (pin "1") (pinfunction "1_1") (pintype "passive"))
      (node (ref "R42") (pin "1") (pinfunction "1_1") (pintype "passive"))
    )
    (net (code "51") (name "/SDA1") (class "Default")
      (node (ref "P5") (pin "2") (pinfunction "2_2") (pintype "passive"))
      (node (ref "R14") (pin "2") (pinfunction "2_2") (pintype "passive"))
      (node (ref "R6") (pin "1") (pinfunction "1_1") (pintype "passive"))
    )
    (net (code "52") (name "/SDA2") (class "Default")
      (node (ref "P4") (pin "1") (pinfunction "1_1") (pintype "passive"))
      (node (ref "R10") (pin "1") (pinfunction "1_1") (pintype "passive"))
      (node (ref "R45") (pin "1") (pinfunction "1_1") (pintype "passive"))
    )
    (net (code "53") (name "3.3V") (class "Default")
      (node (ref "C1") (pin "1") (pinfunction "1_1") (pintype "passive"))
      (node (ref "C2") (pin "1") (pinfunction "1_1") (pintype "passive"))
      (node (ref "C3") (pin "1") (pinfunction "1_1") (pintype "passive"))
      (node (ref "C4") (pin "1") (pinfunction "1_1") (pintype "passive"))
      (node (ref "R10") (pin "2") (pinfunction "2_2") (pintype "passive"))
      (node (ref "R11") (pin "2") (pinfunction "2_2") (pintype "passive"))
      (node (ref "R51") (pin "1") (pinfunction "1_1") (pintype "passive"))
      (node (ref "R6") (pin "2") (pinfunction "2_2") (pintype "passive"))
      (node (ref "R7") (pin "2") (pinfunction "2_2") (pintype "passive"))
      (node (ref "U1") (pin "100") (pinfunction "VDD_100") (pintype "power_in"))
      (node (ref "U1") (pin "11") (pinfunction "VDD_11") (pintype "power_in"))
      (node (ref "U1") (pin "21") (pinfunction "VREF+_21") (pintype "power_in"))
      (node (ref "U1") (pin "22") (pinfunction "VDDA_22") (pintype "power_in"))
      (node (ref "U1") (pin "28") (pinfunction "VDD_28") (pintype "power_in"))
      (node (ref "U1") (pin "50") (pinfunction "VDD_50") (pintype "power_in"))
      (node (ref "U1") (pin "6") (pinfunction "VBAT_6") (pintype "power_in"))
      (node (ref "U1") (pin "75") (pinfunction "VDD_75") (pintype "power_in"))
      (node (ref "X1") (pin "P$1") (pinfunction "2_P$1") (pintype "passive"))
    )
    (net (code "54") (name "GND") (class "Default")
      (node (ref "C1") (pin "2") (pinfunction "2_2") (pintype "passive"))
      (node (ref "C2") (pin "2") (pinfunction "2_2") (pintype "passive"))
      (node (ref "C3") (pin "2") (pinfunction "2_2") (pintype "passive"))
      (node (ref "C4") (pin "2") (pinfunction "2_2") (pintype "passive"))
      (node (ref "C5") (pin "2") (pinfunction "2_2") (pintype "passive"))
      (node (ref "C6") (pin "2") (pinfunction "2_2") (pintype "passive"))
      (node (ref "D1") (pin "2") (pinfunction "2_2") (pintype "passive"))
      (node (ref "D2") (pin "2") (pinfunction "2_2") (pintype "passive"))
      (node (ref "D3") (pin "2") (pinfunction "2_2") (pintype "passive"))
      (node (ref "D4") (pin "2") (pinfunction "2_2") (pintype "passive"))
      (node (ref "D5") (pin "2") (pinfunction "2_2") (pintype "passive"))
      (node (ref "P3") (pin "4") (pinfunction "4_4") (pintype "passive"))
      (node (ref "U1") (pin "10") (pinfunction "VSS_10") (pintype "power_in"))
      (node (ref "U1") (pin "19") (pinfunction "VSSA_19") (pintype "power_in"))
      (node (ref "U1") (pin "20") (pinfunction "VREF-_20") (pintype "power_in"))
      (node (ref "U1") (pin "27") (pinfunction "VSS_27") (pintype "power_in"))
      (node (ref "U1") (pin "49") (pinfunction "VSS_49") (pintype "power_in"))
      (node (ref "U1") (pin "74") (pinfunction "VSS_74") (pintype "power_in"))
      (node (ref "U1") (pin "99") (pinfunction "VSS_99") (pintype "power_in"))
      (node (ref "X1") (pin "P$2") (pinfunction "1_P$2") (pintype "passive"))
      (node (ref "Y1") (pin "2") (pinfunction "2_2") (pintype "passive"))
    )
    (net (code "55") (name "Net-(C6-Pad1)") (class "Default")
      (node (ref "C6") (pin "1") (pinfunction "1_1") (pintype "passive"))
      (node (ref "R60") (pin "2") (pinfunction "2_2") (pintype "passive"))
      (node (ref "R62") (pin "2") (pinfunction "2_2") (pintype "passive"))
      (node (ref "Y1") (pin "3") (pinfunction "3_3") (pintype "passive"))
    )
    (net (code "56") (name "Net-(D1-Pad1)") (class "Default")
      (node (ref "D1") (pin "1") (pinfunction "1_1") (pintype "passive"))
      (node (ref "R5") (pin "2") (pinfunction "2_2") (pintype "passive"))
    )
    (net (code "57") (name "Net-(D2-Pad1)") (class "Default")
      (node (ref "D2") (pin "1") (pinfunction "1_1") (pintype "passive"))
      (node (ref "R8") (pin "2") (pinfunction "2_2") (pintype "passive"))
    )
    (net (code "58") (name "Net-(D3-Pad1)") (class "Default")
      (node (ref "D3") (pin "1") (pinfunction "1_1") (pintype "passive"))
      (node (ref "R9") (pin "2") (pinfunction "2_2") (pintype "passive"))
    )
    (net (code "59") (name "Net-(D4-Pad1)") (class "Default")
      (node (ref "D4") (pin "1") (pinfunction "1_1") (pintype "passive"))
      (node (ref "R12") (pin "2") (pinfunction "2_2") (pintype "passive"))
    )
    (net (code "60") (name "Net-(D5-Pad1)") (class "Default")
      (node (ref "D5") (pin "1") (pinfunction "1_1") (pintype "passive"))
      (node (ref "R51") (pin "2") (pinfunction "2_2") (pintype "passive"))
    )
    (net (code "61") (name "Net-(P1-Pad1)") (class "Default")
      (node (ref "P1") (pin "1") (pinfunction "1_1") (pintype "passive"))
      (node (ref "R1") (pin "2") (pinfunction "2_2") (pintype "passive"))
    )
    (net (code "62") (name "Net-(P1-Pad2)") (class "Default")
      (node (ref "P1") (pin "2") (pinfunction "2_2") (pintype "passive"))
      (node (ref "R13") (pin "2") (pinfunction "2_2") (pintype "passive"))
    )
    (net (code "63") (name "Net-(P1-Pad3)") (class "Default")
      (node (ref "P1") (pin "3") (pinfunction "3_3") (pintype "passive"))
      (node (ref "R17") (pin "2") (pinfunction "2_2") (pintype "passive"))
    )
    (net (code "64") (name "Net-(P2-Pad1)") (class "Default")
      (node (ref "P2") (pin "1") (pinfunction "1_1") (pintype "passive"))
      (node (ref "R3") (pin "2") (pinfunction "2_2") (pintype "passive"))
    )
    (net (code "65") (name "Net-(P2-Pad2)") (class "Default")
      (node (ref "P2") (pin "2") (pinfunction "2_2") (pintype "passive"))
      (node (ref "R15") (pin "2") (pinfunction "2_2") (pintype "passive"))
    )
    (net (code "66") (name "Net-(P2-Pad3)") (class "Default")
      (node (ref "P2") (pin "3") (pinfunction "3_3") (pintype "passive"))
      (node (ref "R19") (pin "2") (pinfunction "2_2") (pintype "passive"))
    )
    (net (code "67") (name "Net-(P2-Pad4)") (class "Default")
      (node (ref "P2") (pin "4") (pinfunction "4_4") (pintype "passive"))
      (node (ref "R22") (pin "2") (pinfunction "2_2") (pintype "passive"))
    )
    (net (code "68") (name "Net-(P2-Pad5)") (class "Default")
      (node (ref "P2") (pin "5") (pinfunction "5_5") (pintype "passive"))
      (node (ref "R24") (pin "2") (pinfunction "2_2") (pintype "passive"))
    )
    (net (code "69") (name "Net-(P2-Pad6)") (class "Default")
      (node (ref "P2") (pin "6") (pinfunction "6_6") (pintype "passive"))
      (node (ref "R26") (pin "2") (pinfunction "2_2") (pintype "passive"))
    )
    (net (code "70") (name "Net-(P2-Pad7)") (class "Default")
      (node (ref "P2") (pin "7") (pinfunction "7_7") (pintype "passive"))
      (node (ref "R28") (pin "2") (pinfunction "2_2") (pintype "passive"))
    )
    (net (code "71") (name "Net-(P2-Pad8)") (class "Default")
      (node (ref "P2") (pin "8") (pinfunction "8_8") (pintype "passive"))
      (node (ref "R30") (pin "2") (pinfunction "2_2") (pintype "passive"))
    )
    (net (code "72") (name "Net-(P2-Pad9)") (class "Default")
      (node (ref "P2") (pin "9") (pinfunction "9_9") (pintype "passive"))
      (node (ref "R32") (pin "2") (pinfunction "2_2") (pintype "passive"))
    )
    (net (code "73") (name "Net-(P2-Pad10)") (class "Default")
      (node (ref "P2") (pin "10") (pinfunction "10_10") (pintype "passive"))
      (node (ref "R34") (pin "2") (pinfunction "2_2") (pintype "passive"))
    )
    (net (code "74") (name "Net-(P2-Pad11)") (class "Default")
      (node (ref "P2") (pin "11") (pinfunction "11_11") (pintype "passive"))
      (node (ref "R36") (pin "2") (pinfunction "2_2") (pintype "passive"))
    )
    (net (code "75") (name "Net-(P2-Pad12)") (class "Default")
      (node (ref "P2") (pin "12") (pinfunction "12_12") (pintype "passive"))
      (node (ref "R38") (pin "2") (pinfunction "2_2") (pintype "passive"))
    )
    (net (code "76") (name "Net-(P2-Pad13)") (class "Default")
      (node (ref "P2") (pin "13") (pinfunction "13_13") (pintype "passive"))
      (node (ref "R41") (pin "2") (pinfunction "2_2") (pintype "passive"))
    )
    (net (code "77") (name "Net-(P2-Pad14)") (class "Default")
      (node (ref "P2") (pin "14") (pinfunction "14_14") (pintype "passive"))
      (node (ref "R44") (pin "2") (pinfunction "2_2") (pintype "passive"))
    )
    (net (code "78") (name "Net-(P2-Pad15)") (class "Default")
      (node (ref "P2") (pin "15") (pinfunction "15_15") (pintype "passive"))
      (node (ref "R47") (pin "2") (pinfunction "2_2") (pintype "passive"))
    )
    (net (code "79") (name "Net-(P2-Pad16)") (class "Default")
      (node (ref "P2") (pin "16") (pinfunction "16_16") (pintype "passive"))
      (node (ref "R50") (pin "2") (pinfunction "2_2") (pintype "passive"))
    )
    (net (code "80") (name "Net-(P2-Pad17)") (class "Default")
      (node (ref "P2") (pin "17") (pinfunction "17_17") (pintype "passive"))
      (node (ref "R54") (pin "2") (pinfunction "2_2") (pintype "passive"))
    )
    (net (code "81") (name "Net-(P2-Pad18)") (class "Default")
      (node (ref "P2") (pin "18") (pinfunction "18_18") (pintype "passive"))
      (node (ref "R56") (pin "2") (pinfunction "2_2") (pintype "passive"))
    )
    (net (code "82") (name "Net-(P2-Pad19)") (class "Default")
      (node (ref "P2") (pin "19") (pinfunction "19_19") (pintype "passive"))
      (node (ref "R58") (pin "2") (pinfunction "2_2") (pintype "passive"))
    )
    (net (code "83") (name "Net-(P2-Pad20)") (class "Default")
      (node (ref "P2") (pin "20") (pinfunction "20_20") (pintype "passive"))
      (node (ref "R59") (pin "2") (pinfunction "2_2") (pintype "passive"))
    )
    (net (code "84") (name "Net-(P3-Pad1)") (class "Default")
      (node (ref "P3") (pin "1") (pinfunction "1_1") (pintype "passive"))
      (node (ref "R4") (pin "2") (pinfunction "2_2") (pintype "passive"))
    )
    (net (code "85") (name "Net-(P3-Pad2)") (class "Default")
      (node (ref "P3") (pin "2") (pinfunction "2_2") (pintype "passive"))
      (node (ref "R16") (pin "2") (pinfunction "2_2") (pintype "passive"))
    )
    (net (code "86") (name "Net-(P3-Pad3)") (class "Default")
      (node (ref "P3") (pin "3") (pinfunction "3_3") (pintype "passive"))
      (node (ref "R20") (pin "2") (pinfunction "2_2") (pintype "passive"))
    )
    (net (code "87") (name "Net-(P4-Pad3)") (class "Default")
      (node (ref "P4") (pin "3") (pinfunction "3_3") (pintype "passive"))
      (node (ref "R18") (pin "2") (pinfunction "2_2") (pintype "passive"))
    )
    (net (code "88") (name "Net-(P4-Pad4)") (class "Default")
      (node (ref "P4") (pin "4") (pinfunction "4_4") (pintype "passive"))
      (node (ref "R21") (pin "2") (pinfunction "2_2") (pintype "passive"))
    )
    (net (code "89") (name "Net-(P4-Pad5)") (class "Default")
      (node (ref "P4") (pin "5") (pinfunction "5_5") (pintype "passive"))
      (node (ref "R23") (pin "2") (pinfunction "2_2") (pintype "passive"))
    )
    (net (code "90") (name "Net-(P4-Pad6)") (class "Default")
      (node (ref "P4") (pin "6") (pinfunction "6_6") (pintype "passive"))
      (node (ref "R25") (pin "2") (pinfunction "2_2") (pintype "passive"))
    )
    (net (code "91") (name "Net-(P4-Pad7)") (class "Default")
      (node (ref "P4") (pin "7") (pinfunction "7_7") (pintype "passive"))
      (node (ref "R27") (pin "2") (pinfunction "2_2") (pintype "passive"))
    )
    (net (code "92") (name "Net-(P4-Pad8)") (class "Default")
      (node (ref "P4") (pin "8") (pinfunction "8_8") (pintype "passive"))
      (node (ref "R29") (pin "2") (pinfunction "2_2") (pintype "passive"))
    )
    (net (code "93") (name "Net-(P4-Pad9)") (class "Default")
      (node (ref "P4") (pin "9") (pinfunction "9_9") (pintype "passive"))
      (node (ref "R31") (pin "2") (pinfunction "2_2") (pintype "passive"))
    )
    (net (code "94") (name "Net-(P4-Pad10)") (class "Default")
      (node (ref "P4") (pin "10") (pinfunction "10_10") (pintype "passive"))
      (node (ref "R33") (pin "2") (pinfunction "2_2") (pintype "passive"))
    )
    (net (code "95") (name "Net-(P4-Pad11)") (class "Default")
      (node (ref "P4") (pin "11") (pinfunction "11_11") (pintype "passive"))
      (node (ref "R35") (pin "2") (pinfunction "2_2") (pintype "passive"))
    )
    (net (code "96") (name "Net-(P4-Pad12)") (class "Default")
      (node (ref "P4") (pin "12") (pinfunction "12_12") (pintype "passive"))
      (node (ref "R37") (pin "2") (pinfunction "2_2") (pintype "passive"))
    )
    (net (code "97") (name "Net-(P4-Pad13)") (class "Default")
      (node (ref "P4") (pin "13") (pinfunction "13_13") (pintype "passive"))
      (node (ref "R40") (pin "2") (pinfunction "2_2") (pintype "passive"))
    )
    (net (code "98") (name "Net-(P4-Pad14)") (class "Default")
      (node (ref "P4") (pin "14") (pinfunction "14_14") (pintype "passive"))
      (node (ref "R43") (pin "2") (pinfunction "2_2") (pintype "passive"))
    )
    (net (code "99") (name "Net-(P4-Pad15)") (class "Default")
      (node (ref "P4") (pin "15") (pinfunction "15_15") (pintype "passive"))
      (node (ref "R46") (pin "2") (pinfunction "2_2") (pintype "passive"))
    )
    (net (code "100") (name "Net-(P4-Pad16)") (class "Default")
      (node (ref "P4") (pin "16") (pinfunction "16_16") (pintype "passive"))
      (node (ref "R49") (pin "2") (pinfunction "2_2") (pintype "passive"))
    )
    (net (code "101") (name "Net-(P4-Pad17)") (class "Default")
      (node (ref "P4") (pin "17") (pinfunction "17_17") (pintype "passive"))
      (node (ref "R53") (pin "2") (pinfunction "2_2") (pintype "passive"))
    )
    (net (code "102") (name "Net-(P5-Pad1)") (class "Default")
      (node (ref "P5") (pin "1") (pinfunction "1_1") (pintype "passive"))
      (node (ref "R39") (pin "2") (pinfunction "2_2") (pintype "passive"))
    )
    (net (code "103") (name "Net-(P5-Pad4)") (class "Default")
      (node (ref "P5") (pin "4") (pinfunction "4_4") (pintype "passive"))
      (node (ref "R48") (pin "2") (pinfunction "2_2") (pintype "passive"))
    )
    (net (code "104") (name "Net-(P5-Pad5)") (class "Default")
      (node (ref "P5") (pin "5") (pinfunction "5_5") (pintype "passive"))
      (node (ref "R52") (pin "2") (pinfunction "2_2") (pintype "passive"))
    )
    (net (code "105") (name "Net-(P5-Pad6)") (class "Default")
      (node (ref "P5") (pin "6") (pinfunction "6_6") (pintype "passive"))
      (node (ref "R55") (pin "2") (pinfunction "2_2") (pintype "passive"))
    )
    (net (code "106") (name "Net-(P5-Pad7)") (class "Default")
      (node (ref "P5") (pin "7") (pinfunction "7_7") (pintype "passive"))
      (node (ref "R57") (pin "2") (pinfunction "2_2") (pintype "passive"))
    )
    (net (code "107") (name "Net-(U1-PB6)") (class "Default")
      (node (ref "R2") (pin "1") (pinfunction "1_1") (pintype "passive"))
      (node (ref "U1") (pin "92") (pinfunction "PB6_92") (pintype "bidirectional"))
    )
    (net (code "108") (name "Net-(U1-PB7)") (class "Default")
      (node (ref "R14") (pin "1") (pinfunction "1_1") (pintype "passive"))
      (node (ref "U1") (pin "93") (pinfunction "PB7_93") (pintype "bidirectional"))
    )
    (net (code "109") (name "Net-(U1-PB10)") (class "Default")
      (node (ref "R42") (pin "2") (pinfunction "2_2") (pintype "passive"))
      (node (ref "U1") (pin "47") (pinfunction "PB10_47") (pintype "bidirectional"))
    )
    (net (code "110") (name "Net-(U1-PB11)") (class "Default")
      (node (ref "R45") (pin "2") (pinfunction "2_2") (pintype "passive"))
      (node (ref "U1") (pin "48") (pinfunction "PB11_48") (pintype "bidirectional"))
    )
    (net (code "111") (name "unconnected-(U1-NC-Pad73)") (class "Default")
      (node (ref "U1") (pin "73") (pinfunction "NC_73") (pintype "bidirectional+no_connect"))
    )
    (net (code "112") (name "unconnected-(U1-PA12-Pad71)") (class "Default")
      (node (ref "U1") (pin "71") (pinfunction "PA12_71") (pintype "bidirectional+no_connect"))
    )
    (net (code "113") (name "unconnected-(U1-PA15-Pad77)") (class "Default")
      (node (ref "U1") (pin "77") (pinfunction "PA15_77") (pintype "bidirectional+no_connect"))
    )
    (net (code "114") (name "unconnected-(U1-PB5-Pad91)") (class "Default")
      (node (ref "U1") (pin "91") (pinfunction "PB5_91") (pintype "bidirectional+no_connect"))
    )
    (net (code "115") (name "unconnected-(U1-PB8-Pad95)") (class "Default")
      (node (ref "U1") (pin "95") (pinfunction "PB8_95") (pintype "bidirectional+no_connect"))
    )
    (net (code "116") (name "unconnected-(U1-PB9-Pad96)") (class "Default")
      (node (ref "U1") (pin "96") (pinfunction "PB9_96") (pintype "bidirectional+no_connect"))
    )
    (net (code "117") (name "unconnected-(U1-PC0-Pad15)") (class "Default")
      (node (ref "U1") (pin "15") (pinfunction "PC0_15") (pintype "bidirectional+no_connect"))
    )
    (net (code "118") (name "unconnected-(U1-PC1-Pad16)") (class "Default")
      (node (ref "U1") (pin "16") (pinfunction "PC1_16") (pintype "bidirectional+no_connect"))
    )
    (net (code "119") (name "unconnected-(U1-PC2-Pad17)") (class "Default")
      (node (ref "U1") (pin "17") (pinfunction "PC2_17") (pintype "bidirectional+no_connect"))
    )
    (net (code "120") (name "unconnected-(U1-PC3-Pad18)") (class "Default")
      (node (ref "U1") (pin "18") (pinfunction "PC3_18") (pintype "bidirectional+no_connect"))
    )
    (net (code "121") (name "unconnected-(U1-PC10-Pad78)") (class "Default")
      (node (ref "U1") (pin "78") (pinfunction "PC10_78") (pintype "bidirectional+no_connect"))
    )
    (net (code "122") (name "unconnected-(U1-PC11-Pad79)") (class "Default")
      (node (ref "U1") (pin "79") (pinfunction "PC11_79") (pintype "bidirectional+no_connect"))
    )
    (net (code "123") (name "unconnected-(U1-PC12-Pad80)") (class "Default")
      (node (ref "U1") (pin "80") (pinfunction "PC12_80") (pintype "bidirectional+no_connect"))
    )
    (net (code "124") (name "unconnected-(U1-PC13-TAMPER-RTC-Pad7)") (class "Default")
      (node (ref "U1") (pin "7") (pinfunction "PC13-TAMPER-RTC_7") (pintype "bidirectional+no_connect"))
    )
    (net (code "125") (name "unconnected-(U1-PC14-OSC32_IN-Pad8)") (class "Default")
      (node (ref "U1") (pin "8") (pinfunction "PC14-OSC32_IN_8") (pintype "bidirectional+no_connect"))
    )
    (net (code "126") (name "unconnected-(U1-PC15-OSC32_OUT-Pad9)") (class "Default")
      (node (ref "U1") (pin "9") (pinfunction "PC15-OSC32_OUT_9") (pintype "bidirectional+no_connect"))
    )
    (net (code "127") (name "unconnected-(U1-PD0-Pad81)") (class "Default")
      (node (ref "U1") (pin "81") (pinfunction "PD0_81") (pintype "bidirectional+no_connect"))
    )
    (net (code "128") (name "unconnected-(U1-PD1-Pad82)") (class "Default")
      (node (ref "U1") (pin "82") (pinfunction "PD1_82") (pintype "bidirectional+no_connect"))
    )
    (net (code "129") (name "unconnected-(U1-PD2-Pad83)") (class "Default")
      (node (ref "U1") (pin "83") (pinfunction "PD2_83") (pintype "bidirectional+no_connect"))
    )
    (net (code "130") (name "unconnected-(U1-PD3-Pad84)") (class "Default")
      (node (ref "U1") (pin "84") (pinfunction "PD3_84") (pintype "bidirectional+no_connect"))
    )
    (net (code "131") (name "unconnected-(U1-PD4-Pad85)") (class "Default")
      (node (ref "U1") (pin "85") (pinfunction "PD4_85") (pintype "bidirectional+no_connect"))
    )
    (net (code "132") (name "unconnected-(U1-PD5-Pad86)") (class "Default")
      (node (ref "U1") (pin "86") (pinfunction "PD5_86") (pintype "bidirectional+no_connect"))
    )
    (net (code "133") (name "unconnected-(U1-PE0-Pad97)") (class "Default")
      (node (ref "U1") (pin "97") (pinfunction "PE0_97") (pintype "bidirectional+no_connect"))
    )
    (net (code "134") (name "unconnected-(U1-PE1-Pad98)") (class "Default")
      (node (ref "U1") (pin "98") (pinfunction "PE1_98") (pintype "power_in+no_connect"))
    )
    (net (code "135") (name "unconnected-(U1-PE2-Pad1)") (class "Default")
      (node (ref "U1") (pin "1") (pinfunction "PE2_1") (pintype "bidirectional+no_connect"))
    )
    (net (code "136") (name "unconnected-(U1-PE3-Pad2)") (class "Default")
      (node (ref "U1") (pin "2") (pinfunction "PE3_2") (pintype "bidirectional+no_connect"))
    )
    (net (code "137") (name "unconnected-(U1-PE4-Pad3)") (class "Default")
      (node (ref "U1") (pin "3") (pinfunction "PE4_3") (pintype "bidirectional+no_connect"))
    )
    (net (code "138") (name "unconnected-(U1-PE5-Pad4)") (class "Default")
      (node (ref "U1") (pin "4") (pinfunction "PE5_4") (pintype "bidirectional+no_connect"))
    )
    (net (code "139") (name "unconnected-(U1-PE6-Pad5)") (class "Default")
      (node (ref "U1") (pin "5") (pinfunction "PE6_5") (pintype "bidirectional+no_connect"))
    )
    (net (code "140") (name "unconnected-(U1-PE8-Pad39)") (class "Default")
      (node (ref "U1") (pin "39") (pinfunction "PE8_39") (pintype "bidirectional+no_connect"))
    )
    (net (code "141") (name "unconnected-(U1-PE10-Pad41)") (class "Default")
      (node (ref "U1") (pin "41") (pinfunction "PE10_41") (pintype "bidirectional+no_connect"))
    )
    (net (code "142") (name "unconnected-(U1-PE14-Pad45)") (class "Default")
      (node (ref "U1") (pin "45") (pinfunction "PE14_45") (pintype "bidirectional+no_connect"))
    )
    (net (code "143") (name "unconnected-(U1-PE15-Pad46)") (class "Default")
      (node (ref "U1") (pin "46") (pinfunction "PE15_46") (pintype "bidirectional+no_connect"))
    )
  )
)
